# FOC_STM32G431.net
KiCad netlist of a schematic drawn in Altium Designer
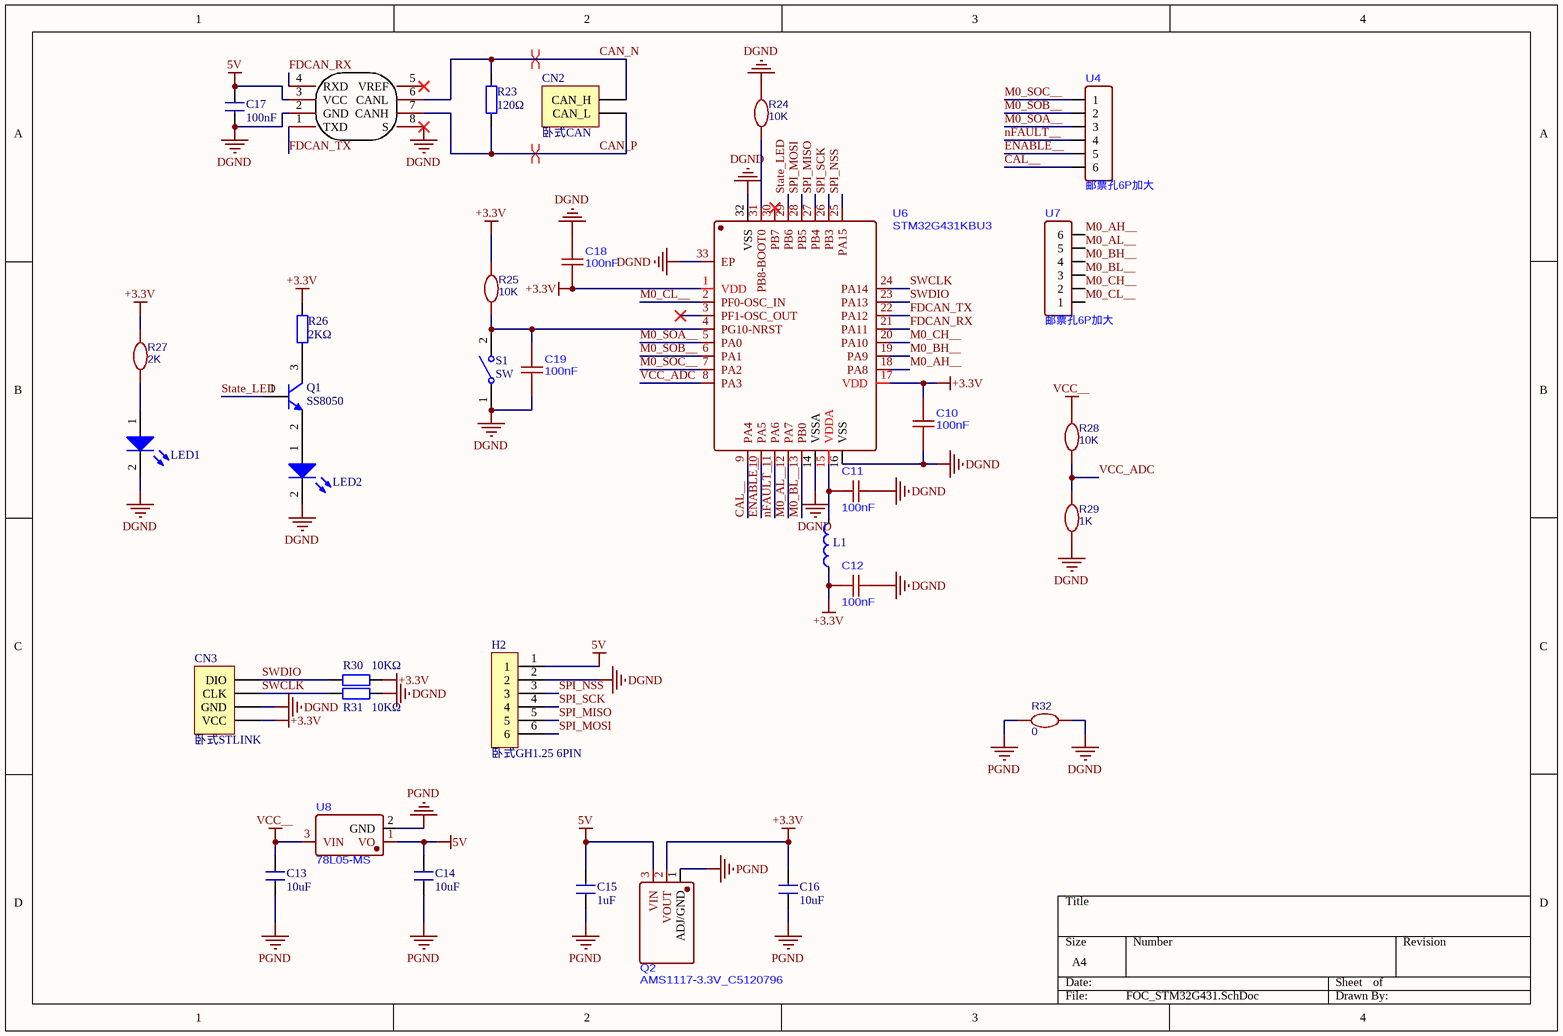
[diagram p0: FOC_STM32G431.SchDoc]

(export (version "E")
  (design (tool "Eeschema 10.0.6"))
  (components
    (comp (ref "C10") (value "100nF") (footprint "c0402") (libsource (lib "PETO") (part "CC0201JRX7R9BB101")))
    (comp (ref "C11") (value "100nF") (footprint "c0402") (libsource (lib "PETO") (part "CC0201JRX7R9BB101")))
    (comp (ref "C12") (value "100nF") (footprint "c0402") (libsource (lib "PETO") (part "CC0201JRX7R9BB101")))
    (comp (ref "C13")
      (value "10uF")
      (footprint "1210")
      (description "1210贴片电容")
      (libsource (lib "Integrated_Library1") (part "1210贴片电容"))
    )
    (comp (ref "C14")
      (value "10uF")
      (footprint "1210")
      (description "1210贴片电容")
      (libsource (lib "Integrated_Library1") (part "1210贴片电容"))
    )
    (comp (ref "C15")
      (value "1uF")
      (footprint "c0402")
      (description "贴片电容0402")
      (libsource (lib "Integrated_Library1") (part "0402贴片电容"))
    )
    (comp (ref "C16")
      (value "10uF")
      (footprint "1210")
      (description "1210贴片电容")
      (libsource (lib "Integrated_Library1") (part "1210贴片电容"))
    )
    (comp (ref "C17")
      (value "100nF")
      (footprint "c0402")
      (description "贴片电容0402")
      (libsource (lib "Integrated_Library1") (part "0402贴片电容"))
    )
    (comp (ref "C18") (value "100nF") (footprint "c0402") (libsource (lib "PETO") (part "CC0201JRX7R9BB101")))
    (comp (ref "C19") (value "100nF") (footprint "c0402") (libsource (lib "PETO") (part "CC0201JRX7R9BB101")))
    (comp (ref "CN2")
      (value "卧式CAN")
      (footprint "GH1.25 2P 卧式")
      (fields (field (name "PUBLISHER") "Altium Limited"))
      (libsource (lib "Integrated_Library1") (part "卧式CAN"))
    )
    (comp (ref "CN3")
      (value "卧式STLINK")
      (footprint "CONN-SMD_4P-P1.25_GH1.25-4P")
      (libsource (lib "Integrated_Library1") (part "卧式STLINK"))
    )
    (comp (ref "H2")
      (value "卧式GH1.25 6PIN")
      (footprint "CONN-SMD_6P-P1.25_XYECONN_XY-GH1.25-6A61")
      (libsource (lib "En") (part "卧式GH1.25 6PIN"))
    )
    (comp (ref "L1")
      (value "1008屏蔽电感")
      (footprint "R0603")
      (libsource (lib "Integrated_Library1") (part "1008屏蔽电感"))
    )
    (comp (ref "LED1")
      (value "LED")
      (footprint "led0805")
      (description "0805贴片LED")
      (libsource (lib "Integrated_Library1") (part "0805贴片LED"))
    )
    (comp (ref "LED2")
      (value "LED")
      (footprint "led0805")
      (description "0805贴片LED")
      (libsource (lib "Integrated_Library1") (part "0805贴片LED"))
    )
    (comp (ref "Q1")
      (value "SS8050")
      (footprint "SOT-23-3_L2.9-W1.3-P1.90-LS2.4-BR")
      (description "三极管")
      (libsource (lib "Integrated_Library1") (part "2N2222"))
    )
    (comp (ref "Q2")
      (value "AMS1117-3.3V_C5120796")
      (footprint "SOT-89-3_L4.5-W2.5-P1.50-LS4.2-BR")
      (libsource (lib "FOC_DRV8323") (part "AMS1117-3.3V_C5120796"))
    )
    (comp (ref "R23")
      (value "120Ω")
      (footprint "R0402")
      (description "0402贴片电阻")
      (libsource (lib "") (part "0402贴片电阻_2"))
    )
    (comp (ref "R24")
      (value "10K")
      (footprint "R0402")
      (fields
        (field (name "BOM_MANUFACTURER PART") "0603WAJ022JT5E")
        (field (name "BOM_SUPPLIER PART") "C25226")
      )
      (libsource (lib "altium-import") (part "root_3_2.2R_"))
    )
    (comp (ref "R25")
      (value "10K")
      (footprint "R0402")
      (fields
        (field (name "BOM_MANUFACTURER PART") "0603WAJ022JT5E")
        (field (name "BOM_SUPPLIER PART") "C25226")
      )
      (libsource (lib "altium-import") (part "root_3_2.2R_"))
    )
    (comp (ref "R26")
      (value "2KΩ")
      (footprint "R0402")
      (description "0402贴片电阻")
      (libsource (lib "") (part "0402贴片电阻_2"))
    )
    (comp (ref "R27")
      (value "2K")
      (footprint "R0402")
      (fields
        (field (name "BOM_MANUFACTURER PART") "0603WAJ022JT5E")
        (field (name "BOM_SUPPLIER PART") "C25226")
      )
      (libsource (lib "altium-import") (part "root_3_2.2R_"))
    )
    (comp (ref "R28")
      (value "10K")
      (footprint "R0402")
      (fields
        (field (name "BOM_MANUFACTURER PART") "0603WAJ022JT5E")
        (field (name "BOM_SUPPLIER PART") "C25226")
      )
      (libsource (lib "altium-import") (part "root_1_2.2R_"))
    )
    (comp (ref "R29")
      (value "1K")
      (footprint "R0402")
      (fields
        (field (name "BOM_MANUFACTURER PART") "0603WAJ022JT5E")
        (field (name "BOM_SUPPLIER PART") "C25226")
      )
      (libsource (lib "altium-import") (part "root_1_2.2R_"))
    )
    (comp (ref "R30")
      (value "10KΩ")
      (footprint "R0402")
      (description "0402贴片电阻")
      (libsource (lib "Integrated_Library1") (part "0402贴片电阻"))
    )
    (comp (ref "R31")
      (value "10KΩ")
      (footprint "R0402")
      (description "0402贴片电阻")
      (libsource (lib "") (part "0402贴片电阻_1"))
    )
    (comp (ref "R32")
      (value "0")
      (footprint "R0402")
      (fields
        (field (name "BOM_MANUFACTURER PART") "0603WAJ022JT5E")
        (field (name "BOM_SUPPLIER PART") "C25226")
      )
      (libsource (lib "altium-import") (part "root_0_2.2R_"))
    )
    (comp (ref "S1")
      (value "SW")
      (footprint "KEY_SMD")
      (description "开关")
      (libsource (lib "Integrated_Library1") (part "SW"))
    )
    (comp (ref "U4")
      (value "邮票孔6P加大")
      (footprint "PCBComponent_1 - duplicate")
      (libsource (lib "FOC_DRV8323") (part "邮票孔6P加大"))
    )
    (comp (ref "U5")
      (value "SN65HVD1050DR")
      (footprint "SOIC-8_L4.9-W3.9-P1.27-LS6.0-BL")
      (description "CAN芯片")
      (fields (field (name "MANUFACTURER") "TI(德州仪器)"))
      (libsource (lib "Integrated_Library1") (part "SN65HVD1050DR"))
    )
    (comp (ref "U6")
      (value "STM32G431KBU3")
      (footprint "UFQFPN-32_L5.0-W5.0-P0.50-BL-EP3.5")
      (libsource (lib "FOC_DRV8323") (part "STM32G431KBU3"))
    )
    (comp (ref "U7")
      (value "邮票孔6P加大")
      (footprint "PCBComponent_1 - duplicate")
      (libsource (lib "FOC_DRV8323") (part "邮票孔6P加大"))
    )
    (comp (ref "U8")
      (value "78L05-MS")
      (footprint "SOT-89-3_L4.5-W2.5-P1.50-LS4.2-BR")
      (libsource (lib "FOC_DRV8323") (part "78L05-MS"))
    )
  )
  (nets
    (net (code "1") (name "+3.3V") (class "Default")
      (node (ref "C10") (pin "2") (pinfunction "2_2") (pintype "passive"))
      (node (ref "C12") (pin "2") (pinfunction "2_2") (pintype "passive"))
      (node (ref "C16") (pin "2") (pinfunction "2_2") (pintype "passive"))
      (node (ref "C18") (pin "2") (pinfunction "2_2") (pintype "passive"))
      (node (ref "CN3") (pin "1") (pinfunction "VCC_1") (pintype "passive"))
      (node (ref "L1") (pin "1") (pinfunction "1_1") (pintype "passive"))
      (node (ref "Q2") (pin "2") (pinfunction "VOUT_2") (pintype "passive"))
      (node (ref "R25") (pin "1") (pinfunction "1_1") (pintype "passive"))
      (node (ref "R26") (pin "2") (pinfunction "2_2") (pintype "passive"))
      (node (ref "R27") (pin "1") (pinfunction "1_1") (pintype "passive"))
      (node (ref "R30") (pin "1") (pinfunction "1_1") (pintype "passive"))
      (node (ref "U6") (pin "1") (pinfunction "VDD_1") (pintype "passive"))
      (node (ref "U6") (pin "17") (pinfunction "VDD_17") (pintype "passive"))
    )
    (net (code "2") (name "/CAL__") (class "Default")
      (node (ref "U4") (pin "1") (pinfunction "6_1") (pintype "passive"))
      (node (ref "U6") (pin "9") (pinfunction "PA4_9") (pintype "passive"))
    )
    (net (code "3") (name "/CAN_N") (class "Default")
      (node (ref "CN2") (pin "1") (pinfunction "CAN_H_1") (pintype "passive"))
      (node (ref "R23") (pin "2") (pinfunction "2_2") (pintype "passive"))
      (node (ref "U5") (pin "6") (pinfunction "CANL_6") (pintype "passive"))
    )
    (net (code "4") (name "/CAN_P") (class "Default")
      (node (ref "CN2") (pin "2") (pinfunction "CAN_L_2") (pintype "passive"))
      (node (ref "R23") (pin "1") (pinfunction "1_1") (pintype "passive"))
      (node (ref "U5") (pin "7") (pinfunction "CANH_7") (pintype "passive"))
    )
    (net (code "5") (name "/ENABLE__") (class "Default")
      (node (ref "U4") (pin "2") (pinfunction "5_2") (pintype "passive"))
      (node (ref "U6") (pin "10") (pinfunction "PA5_10") (pintype "passive"))
    )
    (net (code "6") (name "/FDCAN_RX") (class "Default")
      (node (ref "U5") (pin "4") (pinfunction "RXD_4") (pintype "passive"))
      (node (ref "U6") (pin "21") (pinfunction "PA11_21") (pintype "passive"))
    )
    (net (code "7") (name "/FDCAN_TX") (class "Default")
      (node (ref "U5") (pin "1") (pinfunction "TXD_1") (pintype "passive"))
      (node (ref "U6") (pin "22") (pinfunction "PA12_22") (pintype "passive"))
    )
    (net (code "8") (name "/M0_AH__") (class "Default")
      (node (ref "U6") (pin "18") (pinfunction "PA8_18") (pintype "passive"))
      (node (ref "U7") (pin "1") (pinfunction "6_1") (pintype "passive"))
    )
    (net (code "9") (name "/M0_AL__") (class "Default")
      (node (ref "U6") (pin "12") (pinfunction "PA7_12") (pintype "passive"))
      (node (ref "U7") (pin "2") (pinfunction "5_2") (pintype "passive"))
    )
    (net (code "10") (name "/M0_BH__") (class "Default")
      (node (ref "U6") (pin "19") (pinfunction "PA9_19") (pintype "passive"))
      (node (ref "U7") (pin "3") (pinfunction "4_3") (pintype "passive"))
    )
    (net (code "11") (name "/M0_BL__") (class "Default")
      (node (ref "U6") (pin "13") (pinfunction "PB0_13") (pintype "passive"))
      (node (ref "U7") (pin "4") (pinfunction "3_4") (pintype "passive"))
    )
    (net (code "12") (name "/M0_CH__") (class "Default")
      (node (ref "U6") (pin "20") (pinfunction "PA10_20") (pintype "passive"))
      (node (ref "U7") (pin "5") (pinfunction "2_5") (pintype "passive"))
    )
    (net (code "13") (name "/M0_CL__") (class "Default")
      (node (ref "U6") (pin "2") (pinfunction "PF0-OSC_IN_2") (pintype "passive"))
      (node (ref "U7") (pin "6") (pinfunction "1_6") (pintype "passive"))
    )
    (net (code "14") (name "/M0_SOA__") (class "Default")
      (node (ref "U4") (pin "4") (pinfunction "3_4") (pintype "passive"))
      (node (ref "U6") (pin "5") (pinfunction "PA0_5") (pintype "passive"))
    )
    (net (code "15") (name "/M0_SOB__") (class "Default")
      (node (ref "U4") (pin "5") (pinfunction "2_5") (pintype "passive"))
      (node (ref "U6") (pin "6") (pinfunction "PA1_6") (pintype "passive"))
    )
    (net (code "16") (name "/M0_SOC__") (class "Default")
      (node (ref "U4") (pin "6") (pinfunction "1_6") (pintype "passive"))
      (node (ref "U6") (pin "7") (pinfunction "PA2_7") (pintype "passive"))
    )
    (net (code "17") (name "/SPI_MISO") (class "Default")
      (node (ref "H2") (pin "5") (pinfunction "5_5") (pintype "passive"))
      (node (ref "U6") (pin "27") (pinfunction "PB4_27") (pintype "passive"))
    )
    (net (code "18") (name "/SPI_MOSI") (class "Default")
      (node (ref "H2") (pin "6") (pinfunction "6_6") (pintype "passive"))
      (node (ref "U6") (pin "28") (pinfunction "PB5_28") (pintype "passive"))
    )
    (net (code "19") (name "/SPI_NSS") (class "Default")
      (node (ref "H2") (pin "3") (pinfunction "3_3") (pintype "passive"))
      (node (ref "U6") (pin "25") (pinfunction "PA15_25") (pintype "passive"))
    )
    (net (code "20") (name "/SPI_SCK") (class "Default")
      (node (ref "H2") (pin "4") (pinfunction "4_4") (pintype "passive"))
      (node (ref "U6") (pin "26") (pinfunction "PB3_26") (pintype "passive"))
    )
    (net (code "21") (name "/SWCLK") (class "Default")
      (node (ref "CN3") (pin "3") (pinfunction "CLK_3") (pintype "passive"))
      (node (ref "R31") (pin "1") (pinfunction "1_1") (pintype "passive"))
      (node (ref "U6") (pin "24") (pinfunction "PA14_24") (pintype "passive"))
    )
    (net (code "22") (name "/SWDIO") (class "Default")
      (node (ref "CN3") (pin "4") (pinfunction "DIO_4") (pintype "passive"))
      (node (ref "R30") (pin "2") (pinfunction "2_2") (pintype "passive"))
      (node (ref "U6") (pin "23") (pinfunction "PA13_23") (pintype "passive"))
    )
    (net (code "23") (name "/State_LED") (class "Default")
      (node (ref "Q1") (pin "1") (pinfunction "B_1") (pintype "passive"))
      (node (ref "U6") (pin "29") (pinfunction "PB6_29") (pintype "passive"))
    )
    (net (code "24") (name "/VCC_ADC") (class "Default")
      (node (ref "R28") (pin "1") (pinfunction "1_1") (pintype "passive"))
      (node (ref "R29") (pin "2") (pinfunction "2_2") (pintype "passive"))
      (node (ref "U6") (pin "8") (pinfunction "PA3_8") (pintype "passive"))
    )
    (net (code "25") (name "/nFAULT__") (class "Default")
      (node (ref "U4") (pin "3") (pinfunction "4_3") (pintype "passive"))
      (node (ref "U6") (pin "11") (pinfunction "PA6_11") (pintype "passive"))
    )
    (net (code "26") (name "5V") (class "Default")
      (node (ref "C14") (pin "2") (pinfunction "2_2") (pintype "passive"))
      (node (ref "C15") (pin "2") (pinfunction "2_2") (pintype "passive"))
      (node (ref "C17") (pin "2") (pinfunction "2_2") (pintype "passive"))
      (node (ref "H2") (pin "1") (pinfunction "1_1") (pintype "passive"))
      (node (ref "Q2") (pin "3") (pinfunction "VIN_3") (pintype "passive"))
      (node (ref "U5") (pin "3") (pinfunction "VCC_3") (pintype "passive"))
      (node (ref "U8") (pin "1") (pinfunction "VO_1") (pintype "passive"))
    )
    (net (code "27") (name "DGND") (class "Default")
      (node (ref "C10") (pin "1") (pinfunction "1_1") (pintype "passive"))
      (node (ref "C11") (pin "1") (pinfunction "1_1") (pintype "passive"))
      (node (ref "C12") (pin "1") (pinfunction "1_1") (pintype "passive"))
      (node (ref "C17") (pin "1") (pinfunction "1_1") (pintype "passive"))
      (node (ref "C18") (pin "1") (pinfunction "1_1") (pintype "passive"))
      (node (ref "C19") (pin "1") (pinfunction "1_1") (pintype "passive"))
      (node (ref "CN3") (pin "2") (pinfunction "GND_2") (pintype "passive"))
      (node (ref "H2") (pin "2") (pinfunction "2_2") (pintype "passive"))
      (node (ref "LED1") (pin "2") (pinfunction "K_2") (pintype "passive"))
      (node (ref "LED2") (pin "2") (pinfunction "K_2") (pintype "passive"))
      (node (ref "R24") (pin "1") (pinfunction "1_1") (pintype "passive"))
      (node (ref "R29") (pin "1") (pinfunction "1_1") (pintype "passive"))
      (node (ref "R31") (pin "2") (pinfunction "2_2") (pintype "passive"))
      (node (ref "R32") (pin "2") (pinfunction "2_2") (pintype "passive"))
      (node (ref "S1") (pin "1") (pinfunction "COMMON_1") (pintype "passive"))
      (node (ref "U5") (pin "2") (pinfunction "GND_2") (pintype "passive"))
      (node (ref "U5") (pin "8") (pinfunction "S_8") (pintype "passive"))
      (node (ref "U6") (pin "14") (pinfunction "VSSA_14") (pintype "passive"))
      (node (ref "U6") (pin "16") (pinfunction "VSS_16") (pintype "passive"))
      (node (ref "U6") (pin "32") (pinfunction "VSS_32") (pintype "passive"))
      (node (ref "U6") (pin "33") (pinfunction "EP_33") (pintype "passive"))
    )
    (net (code "28") (name "Net-(LED1-A)") (class "Default")
      (node (ref "LED1") (pin "1") (pinfunction "A_1") (pintype "passive"))
      (node (ref "R27") (pin "2") (pinfunction "2_2") (pintype "passive"))
    )
    (net (code "29") (name "Net-(LED2-A)") (class "Default")
      (node (ref "LED2") (pin "1") (pinfunction "A_1") (pintype "passive"))
      (node (ref "Q1") (pin "2") (pinfunction "E_2") (pintype "passive"))
    )
    (net (code "30") (name "Net-(Q1-C)") (class "Default")
      (node (ref "Q1") (pin "3") (pinfunction "C_3") (pintype "passive"))
      (node (ref "R26") (pin "1") (pinfunction "1_1") (pintype "passive"))
    )
    (net (code "31") (name "Net-(S1-NO)") (class "Default")
      (node (ref "C19") (pin "2") (pinfunction "2_2") (pintype "passive"))
      (node (ref "R25") (pin "2") (pinfunction "2_2") (pintype "passive"))
      (node (ref "S1") (pin "2") (pinfunction "NO_2") (pintype "passive"))
      (node (ref "U6") (pin "4") (pinfunction "PG10-NRST_4") (pintype "passive"))
    )
    (net (code "32") (name "Net-(U6-PB8-BOOT0)") (class "Default")
      (node (ref "R24") (pin "2") (pinfunction "2_2") (pintype "passive"))
      (node (ref "U6") (pin "31") (pinfunction "PB8-BOOT0_31") (pintype "passive"))
    )
    (net (code "33") (name "Net-(U6-VDDA)") (class "Default")
      (node (ref "C11") (pin "2") (pinfunction "2_2") (pintype "passive"))
      (node (ref "L1") (pin "2") (pinfunction "2_2") (pintype "passive"))
      (node (ref "U6") (pin "15") (pinfunction "VDDA_15") (pintype "passive"))
    )
    (net (code "34") (name "PGND") (class "Default")
      (node (ref "C13") (pin "1") (pinfunction "1_1") (pintype "passive"))
      (node (ref "C14") (pin "1") (pinfunction "1_1") (pintype "passive"))
      (node (ref "C15") (pin "1") (pinfunction "1_1") (pintype "passive"))
      (node (ref "C16") (pin "1") (pinfunction "1_1") (pintype "passive"))
      (node (ref "Q2") (pin "1") (pinfunction "ADJ/GND_1") (pintype "passive"))
      (node (ref "R32") (pin "1") (pinfunction "1_1") (pintype "passive"))
      (node (ref "U8") (pin "2") (pinfunction "GND_2") (pintype "passive"))
    )
    (net (code "35") (name "VCC__") (class "Default")
      (node (ref "C13") (pin "2") (pinfunction "2_2") (pintype "passive"))
      (node (ref "R28") (pin "2") (pinfunction "2_2") (pintype "passive"))
      (node (ref "U8") (pin "3") (pinfunction "VIN_3") (pintype "passive"))
    )
    (net (code "36") (name "unconnected-(U5-VREF-Pad5)") (class "Default")
      (node (ref "U5") (pin "5") (pinfunction "VREF_5") (pintype "passive+no_connect"))
    )
    (net (code "37") (name "unconnected-(U6-PB7-Pad30)") (class "Default")
      (node (ref "U6") (pin "30") (pinfunction "PB7_30") (pintype "passive+no_connect"))
    )
    (net (code "38") (name "unconnected-(U6-PF1-OSC_OUT-Pad3)") (class "Default")
      (node (ref "U6") (pin "3") (pinfunction "PF1-OSC_OUT_3") (pintype "passive+no_connect"))
    )
  )
)
